# teensyAdapter.net
KiCad netlist of a schematic drawn in EAGLE
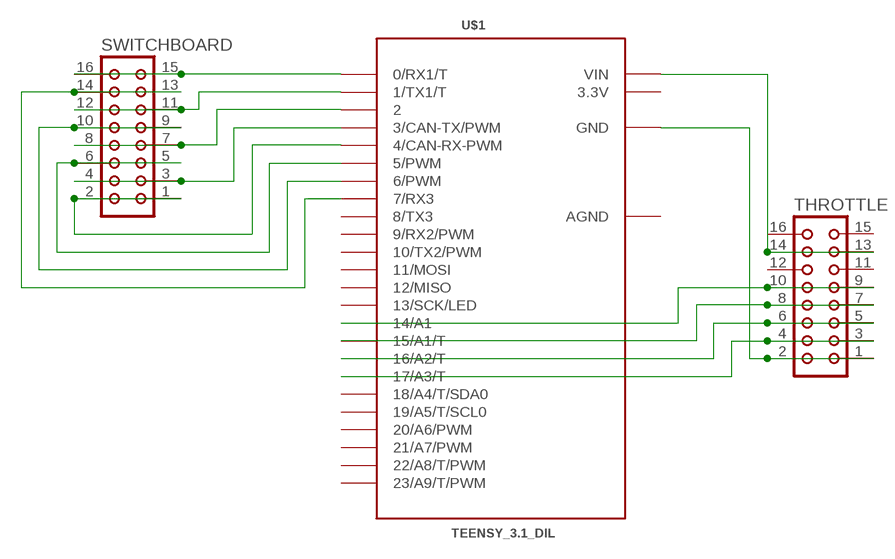
[diagram p0: schematic, sheet 1]

(export (version "E")
  (design (tool "Eeschema 10.0.6"))
  (components
    (comp (ref "SWITCHBOARD")
      (value "CON16")
      (footprint "eagle-import:CON16")
      (libsource (lib "eagle-import") (part "CON16"))
    )
    (comp (ref "THROTTLE")
      (value "CON16")
      (footprint "eagle-import:CON16")
      (libsource (lib "eagle-import") (part "CON16"))
    )
    (comp (ref "U$1")
      (value "TEENSY_3.1_DIL")
      (footprint "eagle-import:TEENSY3-DIL")
      (libsource (lib "eagle-import") (part "TEENSY_3.1_DIL"))
    )
  )
  (nets
    (net (code "1") (name "/3.3V") (class "Default")
      (node (ref "U$1") (pin "3.3V") (pinfunction "3.3V_3.3V") (pintype "power_in"))
    )
    (net (code "2") (name "/AGND") (class "Default")
      (node (ref "U$1") (pin "AGND") (pinfunction "AGND_AGND") (pintype "power_in"))
    )
    (net (code "3") (name "Net-(SWITCHBOARD-Pad7)") (class "Default")
      (node (ref "SWITCHBOARD") (pin "7") (pinfunction "7_7") (pintype "passive"))
      (node (ref "SWITCHBOARD") (pin "8") (pinfunction "8_8") (pintype "passive"))
      (node (ref "U$1") (pin "2") (pinfunction "2_2") (pintype "bidirectional"))
    )
    (net (code "4") (name "Net-(THROTTLE-Pad1)") (class "Default")
      (node (ref "THROTTLE") (pin "1") (pinfunction "1_1") (pintype "passive"))
      (node (ref "THROTTLE") (pin "2") (pinfunction "2_2") (pintype "passive"))
      (node (ref "U$1") (pin "GND") (pinfunction "GND_GND") (pintype "power_in"))
    )
    (net (code "5") (name "Net-(THROTTLE-Pad13)") (class "Default")
      (node (ref "THROTTLE") (pin "13") (pinfunction "13_13") (pintype "passive"))
      (node (ref "THROTTLE") (pin "14") (pinfunction "14_14") (pintype "passive"))
      (node (ref "U$1") (pin "VIN") (pinfunction "VIN_VIN") (pintype "power_in"))
    )
    (net (code "6") (name "Net-(U$1-0{slash}RX1{slash}T)") (class "Default")
      (node (ref "SWITCHBOARD") (pin "15") (pinfunction "15_15") (pintype "passive"))
      (node (ref "SWITCHBOARD") (pin "16") (pinfunction "16_16") (pintype "passive"))
      (node (ref "U$1") (pin "0") (pinfunction "0/RX1/T_0") (pintype "bidirectional"))
    )
    (net (code "7") (name "Net-(U$1-1{slash}TX1{slash}T)") (class "Default")
      (node (ref "SWITCHBOARD") (pin "11") (pinfunction "11_11") (pintype "passive"))
      (node (ref "SWITCHBOARD") (pin "12") (pinfunction "12_12") (pintype "passive"))
      (node (ref "U$1") (pin "1") (pinfunction "1/TX1/T_1") (pintype "bidirectional"))
    )
    (net (code "8") (name "Net-(U$1-3{slash}CAN-TX{slash}PWM)") (class "Default")
      (node (ref "SWITCHBOARD") (pin "3") (pinfunction "3_3") (pintype "passive"))
      (node (ref "SWITCHBOARD") (pin "4") (pinfunction "4_4") (pintype "passive"))
      (node (ref "U$1") (pin "3") (pinfunction "3/CAN-TX/PWM_3") (pintype "bidirectional"))
    )
    (net (code "9") (name "Net-(U$1-4{slash}CAN-RX-PWM)") (class "Default")
      (node (ref "SWITCHBOARD") (pin "1") (pinfunction "1_1") (pintype "passive"))
      (node (ref "SWITCHBOARD") (pin "2") (pinfunction "2_2") (pintype "passive"))
      (node (ref "U$1") (pin "4") (pinfunction "4/CAN-RX-PWM_4") (pintype "bidirectional"))
    )
    (net (code "10") (name "Net-(U$1-5{slash}PWM)") (class "Default")
      (node (ref "SWITCHBOARD") (pin "5") (pinfunction "5_5") (pintype "passive"))
      (node (ref "SWITCHBOARD") (pin "6") (pinfunction "6_6") (pintype "passive"))
      (node (ref "U$1") (pin "5") (pinfunction "5/PWM_5") (pintype "bidirectional"))
    )
    (net (code "11") (name "Net-(U$1-6{slash}PWM)") (class "Default")
      (node (ref "SWITCHBOARD") (pin "10") (pinfunction "10_10") (pintype "passive"))
      (node (ref "SWITCHBOARD") (pin "9") (pinfunction "9_9") (pintype "passive"))
      (node (ref "U$1") (pin "6") (pinfunction "6/PWM_6") (pintype "bidirectional"))
    )
    (net (code "12") (name "Net-(U$1-7{slash}RX3)") (class "Default")
      (node (ref "SWITCHBOARD") (pin "13") (pinfunction "13_13") (pintype "passive"))
      (node (ref "SWITCHBOARD") (pin "14") (pinfunction "14_14") (pintype "passive"))
      (node (ref "U$1") (pin "7") (pinfunction "7/RX3_7") (pintype "bidirectional"))
    )
    (net (code "13") (name "Net-(U$1-14{slash}A1)") (class "Default")
      (node (ref "THROTTLE") (pin "10") (pinfunction "10_10") (pintype "passive"))
      (node (ref "THROTTLE") (pin "9") (pinfunction "9_9") (pintype "passive"))
      (node (ref "U$1") (pin "14/A0") (pinfunction "14/A1_14/A0") (pintype "bidirectional"))
    )
    (net (code "14") (name "Net-(U$1-15{slash}A1{slash}T)") (class "Default")
      (node (ref "THROTTLE") (pin "7") (pinfunction "7_7") (pintype "passive"))
      (node (ref "THROTTLE") (pin "8") (pinfunction "8_8") (pintype "passive"))
      (node (ref "U$1") (pin "15/A1") (pinfunction "15/A1/T_15/A1") (pintype "bidirectional"))
    )
    (net (code "15") (name "Net-(U$1-16{slash}A2{slash}T)") (class "Default")
      (node (ref "THROTTLE") (pin "5") (pinfunction "5_5") (pintype "passive"))
      (node (ref "THROTTLE") (pin "6") (pinfunction "6_6") (pintype "passive"))
      (node (ref "U$1") (pin "16/A2") (pinfunction "16/A2/T_16/A2") (pintype "bidirectional"))
    )
    (net (code "16") (name "Net-(U$1-17{slash}A3{slash}T)") (class "Default")
      (node (ref "THROTTLE") (pin "3") (pinfunction "3_3") (pintype "passive"))
      (node (ref "THROTTLE") (pin "4") (pinfunction "4_4") (pintype "passive"))
      (node (ref "U$1") (pin "17/A3") (pinfunction "17/A3/T_17/A3") (pintype "bidirectional"))
    )
    (net (code "17") (name "unconnected-(THROTTLE-Pad11)") (class "Default")
      (node (ref "THROTTLE") (pin "11") (pinfunction "11_11") (pintype "passive"))
    )
    (net (code "18") (name "unconnected-(THROTTLE-Pad12)") (class "Default")
      (node (ref "THROTTLE") (pin "12") (pinfunction "12_12") (pintype "passive"))
    )
    (net (code "19") (name "unconnected-(THROTTLE-Pad15)") (class "Default")
      (node (ref "THROTTLE") (pin "15") (pinfunction "15_15") (pintype "passive"))
    )
    (net (code "20") (name "unconnected-(THROTTLE-Pad16)") (class "Default")
      (node (ref "THROTTLE") (pin "16") (pinfunction "16_16") (pintype "passive"))
    )
    (net (code "21") (name "unconnected-(U$1-8{slash}TX3-Pad8)") (class "Default")
      (node (ref "U$1") (pin "8") (pinfunction "8/TX3_8") (pintype "bidirectional"))
    )
    (net (code "22") (name "unconnected-(U$1-9{slash}RX2{slash}PWM-Pad9)") (class "Default")
      (node (ref "U$1") (pin "9") (pinfunction "9/RX2/PWM_9") (pintype "bidirectional"))
    )
    (net (code "23") (name "unconnected-(U$1-10{slash}TX2{slash}PWM-Pad10)") (class "Default")
      (node (ref "U$1") (pin "10") (pinfunction "10/TX2/PWM_10") (pintype "bidirectional"))
    )
    (net (code "24") (name "unconnected-(U$1-11{slash}MOSI-Pad11)") (class "Default")
      (node (ref "U$1") (pin "11") (pinfunction "11/MOSI_11") (pintype "bidirectional"))
    )
    (net (code "25") (name "unconnected-(U$1-12{slash}MISO-Pad12)") (class "Default")
      (node (ref "U$1") (pin "12") (pinfunction "12/MISO_12") (pintype "bidirectional"))
    )
    (net (code "26") (name "unconnected-(U$1-13{slash}SCK{slash}LED-Pad13)") (class "Default")
      (node (ref "U$1") (pin "13") (pinfunction "13/SCK/LED_13") (pintype "bidirectional"))
    )
    (net (code "27") (name "unconnected-(U$1-18{slash}A4{slash}T{slash}SDA0-Pad18{slash}A4)") (class "Default")
      (node (ref "U$1") (pin "18/A4") (pinfunction "18/A4/T/SDA0_18/A4") (pintype "bidirectional"))
    )
    (net (code "28") (name "unconnected-(U$1-19{slash}A5{slash}T{slash}SCL0-Pad19{slash}A5)") (class "Default")
      (node (ref "U$1") (pin "19/A5") (pinfunction "19/A5/T/SCL0_19/A5") (pintype "bidirectional"))
    )
    (net (code "29") (name "unconnected-(U$1-20{slash}A6{slash}PWM-Pad20{slash}A6)") (class "Default")
      (node (ref "U$1") (pin "20/A6") (pinfunction "20/A6/PWM_20/A6") (pintype "bidirectional"))
    )
    (net (code "30") (name "unconnected-(U$1-21{slash}A7{slash}PWM-Pad21{slash}A7)") (class "Default")
      (node (ref "U$1") (pin "21/A7") (pinfunction "21/A7/PWM_21/A7") (pintype "bidirectional"))
    )
    (net (code "31") (name "unconnected-(U$1-22{slash}A8{slash}T{slash}PWM-Pad22{slash}A8)") (class "Default")
      (node (ref "U$1") (pin "22/A8") (pinfunction "22/A8/T/PWM_22/A8") (pintype "bidirectional"))
    )
    (net (code "32") (name "unconnected-(U$1-23{slash}A9{slash}T{slash}PWM-Pad23{slash}A9)") (class "Default")
      (node (ref "U$1") (pin "23/A9") (pinfunction "23/A9/T/PWM_23/A9") (pintype "bidirectional"))
    )
  )
)
